# MOTOR_CUR_SENS.net
KiCad netlist of a schematic drawn in Altium Designer
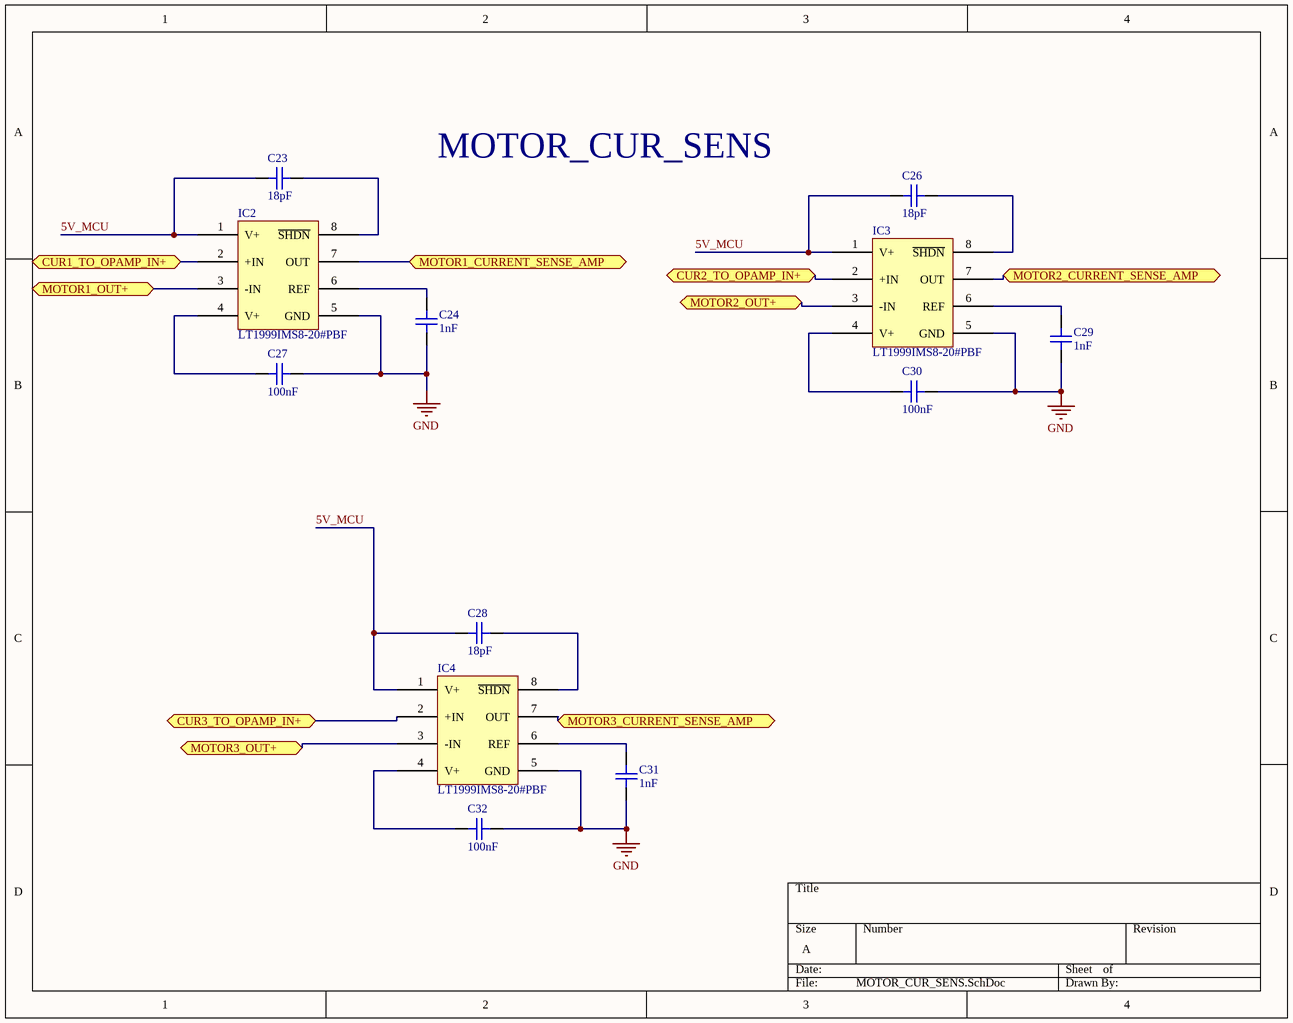
[diagram p0: MOTOR_CUR_SENS.SchDoc]

(export (version "E")
  (design (tool "Eeschema 10.0.6"))
  (components
    (comp (ref "C23")
      (value "18pF")
      (footprint "CAP_ADJ_0805")
      (description "CERAMIC CAPACITOR SMD 0805")
      (fields
        (field (name "MANUFACTURER") "Yageo")
        (field (name "MANUFACTURER PART NUMBER") "CC0805FRNPO9BN180")
      )
      (libsource (lib "ORI_MANIPULATOR_BRD") (part "CAP_ADJ_0805"))
    )
    (comp (ref "C24")
      (value "1nF")
      (footprint "CAP_ADJ_0805")
      (description "CERAMIC CAPACITOR SMD 0805")
      (fields
        (field (name "MANUFACTURER") "KEMET")
        (field (name "MANUFACTURER PART NUMBER") "C0805C102K4RACTU")
      )
      (libsource (lib "ORI_MANIPULATOR_BRD") (part "CAP_ADJ_0805"))
    )
    (comp (ref "C26")
      (value "18pF")
      (footprint "CAP_ADJ_0805")
      (description "CERAMIC CAPACITOR SMD 0805")
      (fields
        (field (name "MANUFACTURER") "Yageo")
        (field (name "MANUFACTURER PART NUMBER") "CC0805FRNPO9BN180")
      )
      (libsource (lib "ORI_MANIPULATOR_BRD") (part "CAP_ADJ_0805"))
    )
    (comp (ref "C27")
      (value "100nF")
      (footprint "CAP_ADJ_0805")
      (description "CERAMIC CAPACITOR SMD 0805")
      (fields
        (field (name "MANUFACTURER") "KEMET")
        (field (name "MANUFACTURER PART NUMBER") "C0805C104J5RACAUTO")
      )
      (libsource (lib "ORI_MANIPULATOR_BRD") (part "CAP_ADJ_0805"))
    )
    (comp (ref "C28")
      (value "18pF")
      (footprint "CAP_ADJ_0805")
      (description "CERAMIC CAPACITOR SMD 0805")
      (fields
        (field (name "MANUFACTURER") "Yageo")
        (field (name "MANUFACTURER PART NUMBER") "CC0805FRNPO9BN180")
      )
      (libsource (lib "ORI_MANIPULATOR_BRD") (part "CAP_ADJ_0805"))
    )
    (comp (ref "C29")
      (value "1nF")
      (footprint "CAP_ADJ_0805")
      (description "CERAMIC CAPACITOR SMD 0805")
      (fields
        (field (name "MANUFACTURER") "KEMET")
        (field (name "MANUFACTURER PART NUMBER") "C0805C102K4RACTU")
      )
      (libsource (lib "ORI_MANIPULATOR_BRD") (part "CAP_ADJ_0805"))
    )
    (comp (ref "C30")
      (value "100nF")
      (footprint "CAP_ADJ_0805")
      (description "CERAMIC CAPACITOR SMD 0805")
      (fields
        (field (name "MANUFACTURER") "KEMET")
        (field (name "MANUFACTURER PART NUMBER") "C0805C104J5RACAUTO")
      )
      (libsource (lib "ORI_MANIPULATOR_BRD") (part "CAP_ADJ_0805"))
    )
    (comp (ref "C31")
      (value "1nF")
      (footprint "CAP_ADJ_0805")
      (description "CERAMIC CAPACITOR SMD 0805")
      (fields
        (field (name "MANUFACTURER") "KEMET")
        (field (name "MANUFACTURER PART NUMBER") "C0805C102K4RACTU")
      )
      (libsource (lib "ORI_MANIPULATOR_BRD") (part "CAP_ADJ_0805"))
    )
    (comp (ref "C32")
      (value "100nF")
      (footprint "CAP_ADJ_0805")
      (description "CERAMIC CAPACITOR SMD 0805")
      (fields
        (field (name "MANUFACTURER") "KEMET")
        (field (name "MANUFACTURER PART NUMBER") "C0805C104J5RACAUTO")
      )
      (libsource (lib "ORI_MANIPULATOR_BRD") (part "CAP_ADJ_0805"))
    )
    (comp (ref "IC2")
      (value "LT1999IMS8-20#PBF")
      (footprint "LT1999IMS8-20#PBF-ND")
      (description "IC OPAMP CURR SENSE 2MHZ 8MSOP")
      (fields (field (name "MANUFACTURER") "Analog Devices / Linear Technology"))
      (libsource (lib "ORI_MANIPULATOR_BRD") (part "LT1999IMS8-20#PBF"))
    )
    (comp (ref "IC3")
      (value "LT1999IMS8-20#PBF")
      (footprint "LT1999IMS8-20#PBF-ND")
      (description "IC OPAMP CURR SENSE 2MHZ 8MSOP")
      (fields (field (name "MANUFACTURER") "Analog Devices / Linear Technology"))
      (libsource (lib "ORI_MANIPULATOR_BRD") (part "LT1999IMS8-20#PBF"))
    )
    (comp (ref "IC4")
      (value "LT1999IMS8-20#PBF")
      (footprint "LT1999IMS8-20#PBF-ND")
      (description "IC OPAMP CURR SENSE 2MHZ 8MSOP")
      (fields (field (name "MANUFACTURER") "Analog Devices / Linear Technology"))
      (libsource (lib "ORI_MANIPULATOR_BRD") (part "LT1999IMS8-20#PBF"))
    )
  )
  (nets
    (net (code "1") (name "/5V_MCU") (class "Default")
      (node (ref "C23") (pin "2") (pinfunction "2_2") (pintype "passive"))
      (node (ref "C26") (pin "2") (pinfunction "2_2") (pintype "passive"))
      (node (ref "C28") (pin "2") (pinfunction "2_2") (pintype "passive"))
      (node (ref "IC2") (pin "1") (pinfunction "V+_1") (pintype "passive"))
      (node (ref "IC3") (pin "1") (pinfunction "V+_1") (pintype "passive"))
      (node (ref "IC4") (pin "1") (pinfunction "V+_1") (pintype "passive"))
    )
    (net (code "2") (name "/CUR1_TO_OPAMP_IN+") (class "Default")
      (node (ref "IC2") (pin "2") (pinfunction "+IN_2") (pintype "passive"))
    )
    (net (code "3") (name "/CUR2_TO_OPAMP_IN+") (class "Default")
      (node (ref "IC3") (pin "2") (pinfunction "+IN_2") (pintype "passive"))
    )
    (net (code "4") (name "/CUR3_TO_OPAMP_IN+") (class "Default")
      (node (ref "IC4") (pin "2") (pinfunction "+IN_2") (pintype "passive"))
    )
    (net (code "5") (name "/MOTOR1_CURRENT_SENSE_AMP") (class "Default")
      (node (ref "IC2") (pin "7") (pinfunction "OUT_7") (pintype "passive"))
    )
    (net (code "6") (name "/MOTOR1_OUT+") (class "Default")
      (node (ref "IC2") (pin "3") (pinfunction "-IN_3") (pintype "passive"))
    )
    (net (code "7") (name "/MOTOR2_CURRENT_SENSE_AMP") (class "Default")
      (node (ref "IC3") (pin "7") (pinfunction "OUT_7") (pintype "passive"))
    )
    (net (code "8") (name "/MOTOR2_OUT+") (class "Default")
      (node (ref "IC3") (pin "3") (pinfunction "-IN_3") (pintype "passive"))
    )
    (net (code "9") (name "/MOTOR3_CURRENT_SENSE_AMP") (class "Default")
      (node (ref "IC4") (pin "7") (pinfunction "OUT_7") (pintype "passive"))
    )
    (net (code "10") (name "/MOTOR3_OUT+") (class "Default")
      (node (ref "IC4") (pin "3") (pinfunction "-IN_3") (pintype "passive"))
    )
    (net (code "11") (name "GND") (class "Default")
      (node (ref "C24") (pin "1") (pinfunction "1_1") (pintype "passive"))
      (node (ref "C27") (pin "1") (pinfunction "1_1") (pintype "passive"))
      (node (ref "C29") (pin "1") (pinfunction "1_1") (pintype "passive"))
      (node (ref "C30") (pin "1") (pinfunction "1_1") (pintype "passive"))
      (node (ref "C31") (pin "1") (pinfunction "1_1") (pintype "passive"))
      (node (ref "C32") (pin "1") (pinfunction "1_1") (pintype "passive"))
      (node (ref "IC2") (pin "5") (pinfunction "GND_5") (pintype "passive"))
      (node (ref "IC3") (pin "5") (pinfunction "GND_5") (pintype "passive"))
      (node (ref "IC4") (pin "5") (pinfunction "GND_5") (pintype "passive"))
    )
    (net (code "12") (name "Net-(C27-Pad2)") (class "Default")
      (node (ref "C27") (pin "2") (pinfunction "2_2") (pintype "passive"))
      (node (ref "IC2") (pin "4") (pinfunction "V+_4") (pintype "passive"))
    )
    (net (code "13") (name "Net-(C30-Pad2)") (class "Default")
      (node (ref "C30") (pin "2") (pinfunction "2_2") (pintype "passive"))
      (node (ref "IC3") (pin "4") (pinfunction "V+_4") (pintype "passive"))
    )
    (net (code "14") (name "Net-(C32-Pad2)") (class "Default")
      (node (ref "C32") (pin "2") (pinfunction "2_2") (pintype "passive"))
      (node (ref "IC4") (pin "4") (pinfunction "V+_4") (pintype "passive"))
    )
    (net (code "15") (name "Net-(IC2-REF)") (class "Default")
      (node (ref "C24") (pin "2") (pinfunction "2_2") (pintype "passive"))
      (node (ref "IC2") (pin "6") (pinfunction "REF_6") (pintype "passive"))
    )
    (net (code "16") (name "Net-(IC2-~{SHDN})") (class "Default")
      (node (ref "C23") (pin "1") (pinfunction "1_1") (pintype "passive"))
      (node (ref "IC2") (pin "8") (pinfunction "~{SHDN}_8") (pintype "passive"))
    )
    (net (code "17") (name "Net-(IC3-REF)") (class "Default")
      (node (ref "C29") (pin "2") (pinfunction "2_2") (pintype "passive"))
      (node (ref "IC3") (pin "6") (pinfunction "REF_6") (pintype "passive"))
    )
    (net (code "18") (name "Net-(IC3-~{SHDN})") (class "Default")
      (node (ref "C26") (pin "1") (pinfunction "1_1") (pintype "passive"))
      (node (ref "IC3") (pin "8") (pinfunction "~{SHDN}_8") (pintype "passive"))
    )
    (net (code "19") (name "Net-(IC4-REF)") (class "Default")
      (node (ref "C31") (pin "2") (pinfunction "2_2") (pintype "passive"))
      (node (ref "IC4") (pin "6") (pinfunction "REF_6") (pintype "passive"))
    )
    (net (code "20") (name "Net-(IC4-~{SHDN})") (class "Default")
      (node (ref "C28") (pin "1") (pinfunction "1_1") (pintype "passive"))
      (node (ref "IC4") (pin "8") (pinfunction "~{SHDN}_8") (pintype "passive"))
    )
  )
)
